# IARC_GR_Shield_SMD.net
KiCad netlist of a schematic drawn in EAGLE
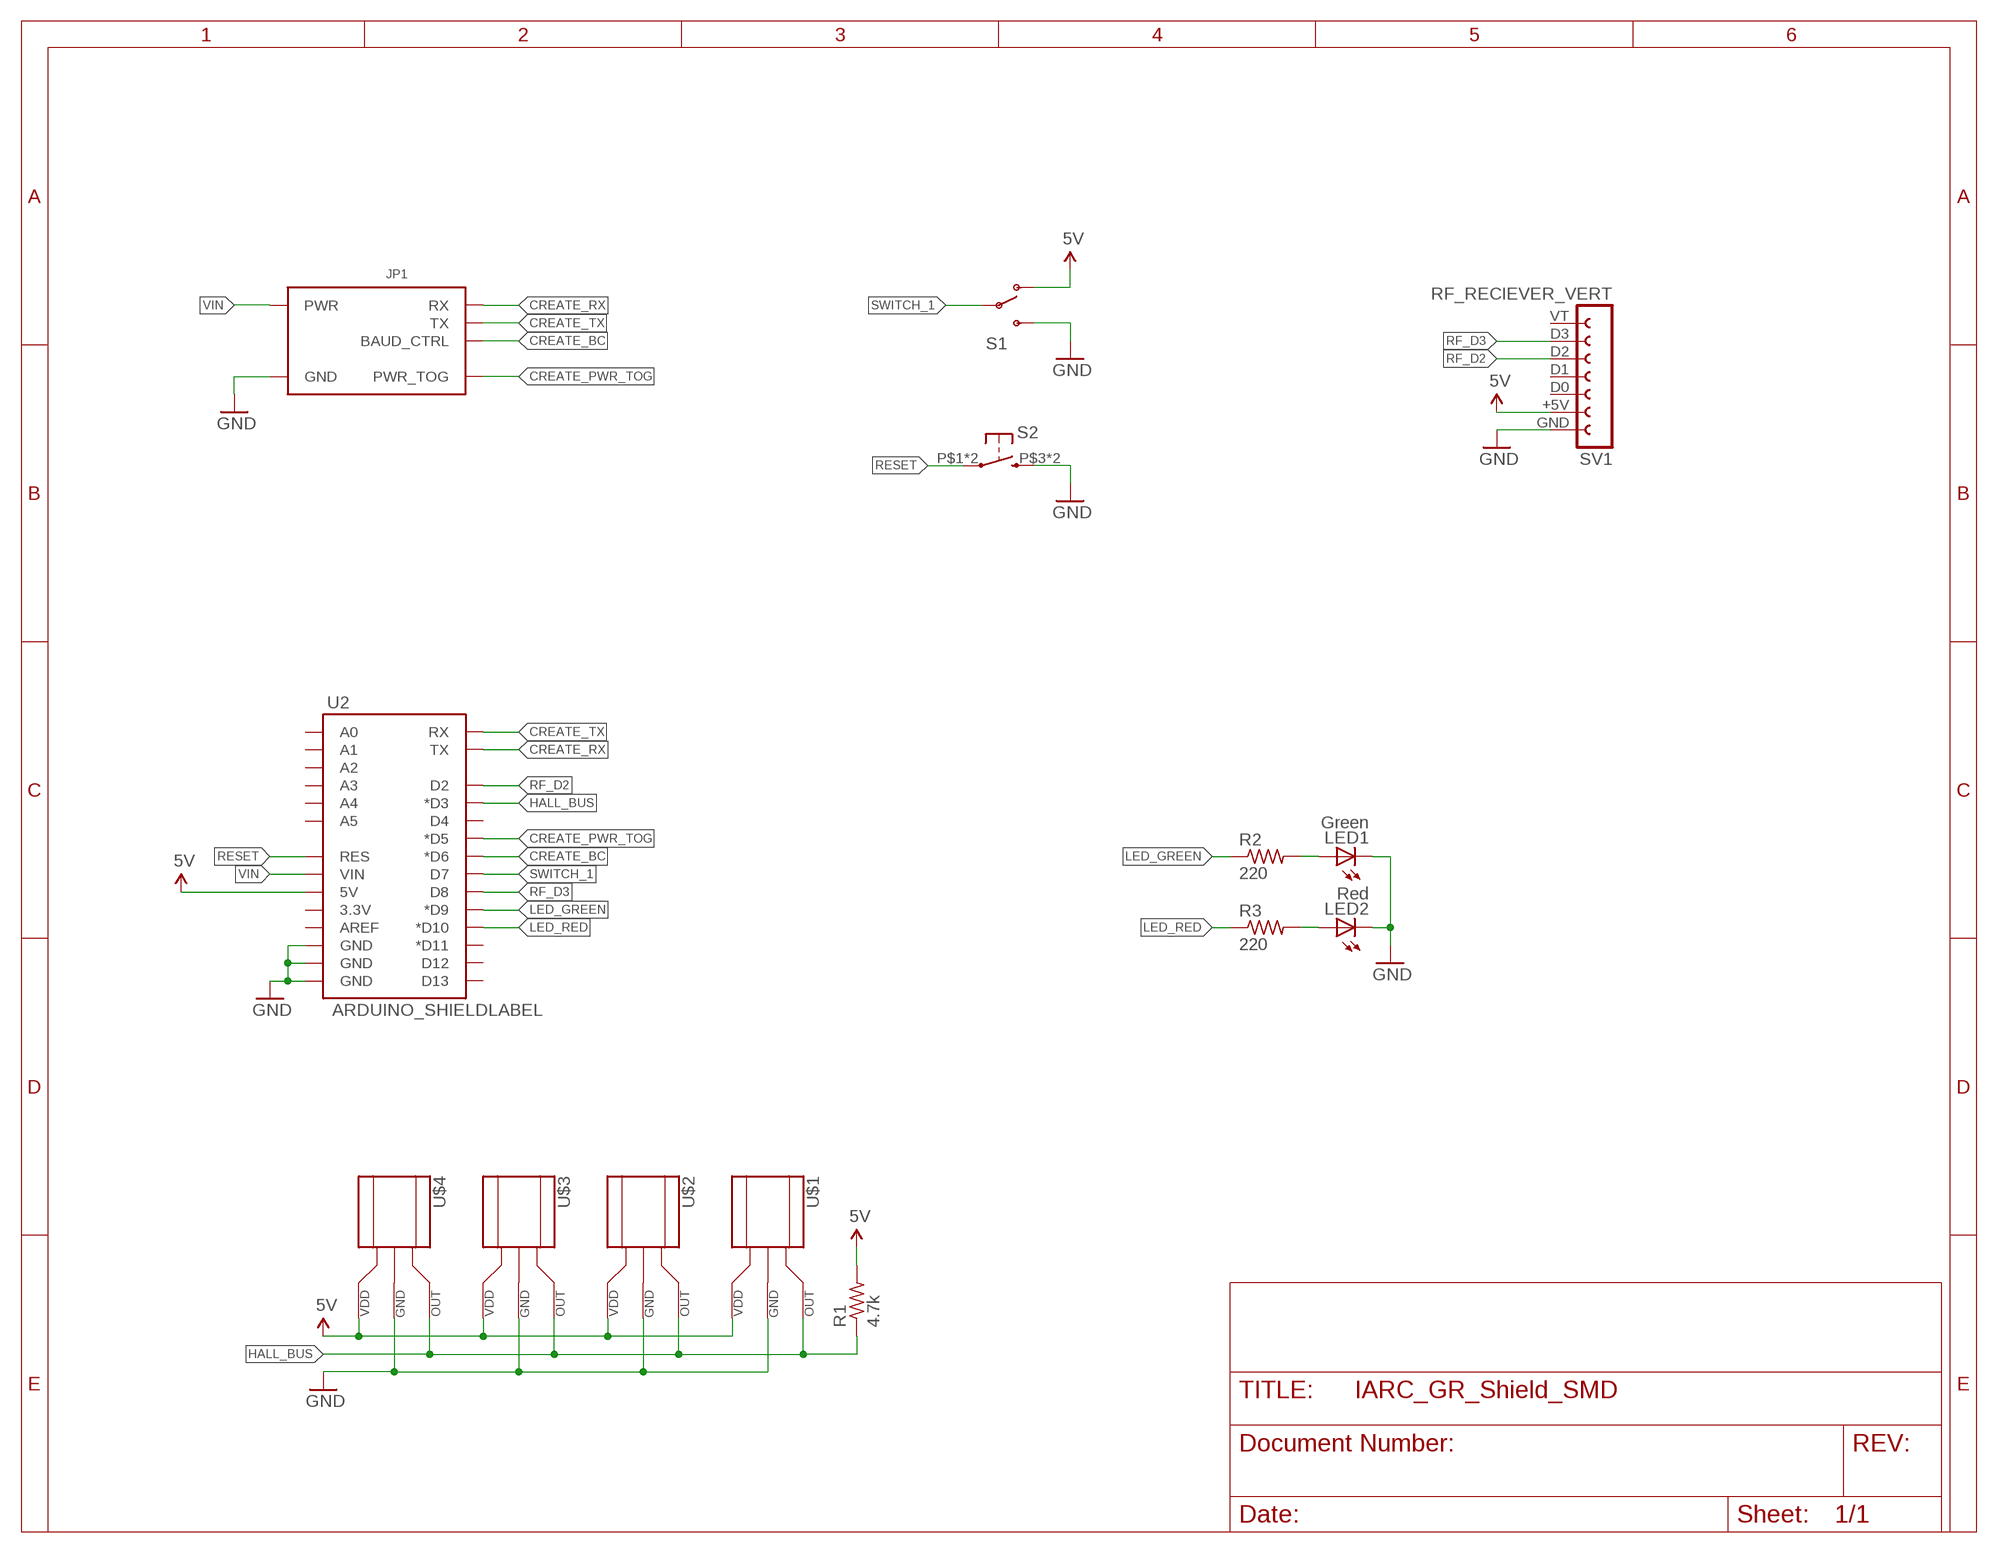
[diagram p0: schematic, sheet 1]

(export (version "E")
  (design (tool "Eeschema 10.0.6"))
  (components
    (comp (ref "JP1")
      (value "IROBOT_CREATE_IARC_HOOKUP")
      (footprint "eagle-import:2X5-SHROUDED")
      (libsource (lib "eagle-import") (part "IROBOT_CREATE_IARC_HOOKUP"))
    )
    (comp (ref "LED1")
      (value "Green")
      (footprint "eagle-import:CHIPLED_0603")
      (libsource (lib "eagle-import") (part "LEDCHIPLED_0603"))
    )
    (comp (ref "LED2")
      (value "Red")
      (footprint "eagle-import:CHIPLED_0603")
      (libsource (lib "eagle-import") (part "LEDCHIPLED_0603"))
    )
    (comp (ref "R1")
      (value "4.7k")
      (footprint "eagle-import:R0603")
      (libsource (lib "eagle-import") (part "R-USR0603"))
    )
    (comp (ref "R2")
      (value "220")
      (footprint "eagle-import:R0603")
      (fields (field (name "DIGIKEY#") "P220HCT-ND"))
      (libsource (lib "eagle-import") (part "R-USR0603"))
    )
    (comp (ref "R3")
      (value "220")
      (footprint "eagle-import:R0603")
      (fields (field (name "DIGIKEY#") "P220HCT-ND"))
      (libsource (lib "eagle-import") (part "R-USR0603"))
    )
    (comp (ref "S1")
      (value "SWITCH-SPDTTHRU-VERT")
      (footprint "eagle-import:SWITCH-SPDT_THRU-VERT")
      (libsource (lib "eagle-import") (part "SWITCH-SPDTTHRU-VERT"))
    )
    (comp (ref "S2")
      (value "TACT_BUTTON_SMD")
      (footprint "eagle-import:SIMPLE_BUTTON_SMD")
      (libsource (lib "eagle-import") (part "TACT_BUTTON_SMD"))
    )
    (comp (ref "SV1")
      (value "RF_RECIEVER_VERT")
      (footprint "eagle-import:RF_RECIEVER_VERT")
      (fields (field (name "MF") "Sulins") (field (name "MPN") "PPTC071LFBN-RC"))
      (libsource (lib "eagle-import") (part "RF_RECIEVER_VERT"))
    )
    (comp (ref "U$1")
      (value "HALL_EFFECTHEADER")
      (footprint "eagle-import:1X03")
      (fields (field (name "MFR") "FCI") (field (name "MPN") "68000-103HLF"))
      (libsource (lib "eagle-import") (part "HALL_EFFECTHEADER"))
    )
    (comp (ref "U$2")
      (value "HALL_EFFECTHEADER")
      (footprint "eagle-import:1X03")
      (fields (field (name "MFR") "FCI") (field (name "MPN") "68000-103HLF"))
      (libsource (lib "eagle-import") (part "HALL_EFFECTHEADER"))
    )
    (comp (ref "U$3")
      (value "HALL_EFFECTHEADER")
      (footprint "eagle-import:1X03")
      (fields (field (name "MFR") "FCI") (field (name "MPN") "68000-103HLF"))
      (libsource (lib "eagle-import") (part "HALL_EFFECTHEADER"))
    )
    (comp (ref "U$4")
      (value "HALL_EFFECTHEADER")
      (footprint "eagle-import:1X03")
      (fields (field (name "MFR") "FCI") (field (name "MPN") "68000-103HLF"))
      (libsource (lib "eagle-import") (part "HALL_EFFECTHEADER"))
    )
    (comp (ref "U2")
      (value "ARDUINO_SHIELDLABEL")
      (footprint "eagle-import:DUEMILANOVE_SHIELD")
      (libsource (lib "eagle-import") (part "ARDUINO_SHIELDLABEL"))
    )
  )
  (nets
    (net (code "1") (name "5V") (class "Default")
      (node (ref "R1") (pin "2") (pinfunction "2_2") (pintype "passive"))
      (node (ref "S1") (pin "1") (pinfunction "O_1") (pintype "passive"))
      (node (ref "SV1") (pin "+5V") (pinfunction "+5V_+5V") (pintype "power_in"))
      (node (ref "U$1") (pin "1") (pinfunction "VDD_1") (pintype "power_in"))
      (node (ref "U$2") (pin "1") (pinfunction "VDD_1") (pintype "power_in"))
      (node (ref "U$3") (pin "1") (pinfunction "VDD_1") (pintype "power_in"))
      (node (ref "U$4") (pin "1") (pinfunction "VDD_1") (pintype "power_in"))
      (node (ref "U2") (pin "5V") (pinfunction "5V_5V") (pintype "bidirectional"))
    )
    (net (code "2") (name "CREATE_BC") (class "Default")
      (node (ref "JP1") (pin "3") (pinfunction "BAUD_CTRL_3") (pintype "bidirectional"))
      (node (ref "U2") (pin "D6") (pinfunction "*D6_D6") (pintype "bidirectional"))
    )
    (net (code "3") (name "CREATE_PWR_TOG") (class "Default")
      (node (ref "JP1") (pin "5") (pinfunction "PWR_TOG_5") (pintype "bidirectional"))
      (node (ref "U2") (pin "D5") (pinfunction "*D5_D5") (pintype "bidirectional"))
    )
    (net (code "4") (name "CREATE_RX") (class "Default")
      (node (ref "JP1") (pin "4") (pinfunction "RX_4") (pintype "bidirectional"))
      (node (ref "U2") (pin "TX") (pinfunction "TX_TX") (pintype "bidirectional"))
    )
    (net (code "5") (name "CREATE_TX") (class "Default")
      (node (ref "JP1") (pin "1") (pinfunction "TX_1") (pintype "bidirectional"))
      (node (ref "U2") (pin "RX") (pinfunction "RX_RX") (pintype "bidirectional"))
    )
    (net (code "6") (name "GND") (class "Default")
      (node (ref "JP1") (pin "2") (pinfunction "GND_2") (pintype "power_in"))
      (node (ref "LED1") (pin "C") (pinfunction "C_C") (pintype "passive"))
      (node (ref "LED2") (pin "C") (pinfunction "C_C") (pintype "passive"))
      (node (ref "S1") (pin "3") (pinfunction "S_3") (pintype "passive"))
      (node (ref "S2") (pin "P$3") (pinfunction "S_P$3") (pintype "passive"))
      (node (ref "S2") (pin "P$4") (pinfunction "S_P$4") (pintype "passive"))
      (node (ref "SV1") (pin "GND") (pinfunction "GND_GND") (pintype "power_in"))
      (node (ref "U$1") (pin "2") (pinfunction "GND_2") (pintype "power_in"))
      (node (ref "U$2") (pin "2") (pinfunction "GND_2") (pintype "power_in"))
      (node (ref "U$3") (pin "2") (pinfunction "GND_2") (pintype "power_in"))
      (node (ref "U$4") (pin "2") (pinfunction "GND_2") (pintype "power_in"))
      (node (ref "U2") (pin "GND@0") (pinfunction "GND_GND@0") (pintype "bidirectional"))
      (node (ref "U2") (pin "GND@1") (pinfunction "GND_GND@1") (pintype "bidirectional"))
      (node (ref "U2") (pin "GND@2") (pinfunction "GND_GND@2") (pintype "bidirectional"))
    )
    (net (code "7") (name "HALL_BUS") (class "Default")
      (node (ref "R1") (pin "1") (pinfunction "1_1") (pintype "passive"))
      (node (ref "U$1") (pin "3") (pinfunction "OUT_3") (pintype "passive"))
      (node (ref "U$2") (pin "3") (pinfunction "OUT_3") (pintype "passive"))
      (node (ref "U$3") (pin "3") (pinfunction "OUT_3") (pintype "passive"))
      (node (ref "U$4") (pin "3") (pinfunction "OUT_3") (pintype "passive"))
      (node (ref "U2") (pin "D3") (pinfunction "*D3_D3") (pintype "bidirectional"))
    )
    (net (code "8") (name "LED_GREEN") (class "Default")
      (node (ref "R2") (pin "1") (pinfunction "1_1") (pintype "passive"))
      (node (ref "U2") (pin "D9") (pinfunction "*D9_D9") (pintype "bidirectional"))
    )
    (net (code "9") (name "LED_RED") (class "Default")
      (node (ref "R3") (pin "1") (pinfunction "1_1") (pintype "passive"))
      (node (ref "U2") (pin "D10") (pinfunction "*D10_D10") (pintype "bidirectional"))
    )
    (net (code "10") (name "Net-(LED1-PadA)") (class "Default")
      (node (ref "LED1") (pin "A") (pinfunction "A_A") (pintype "passive"))
      (node (ref "R2") (pin "2") (pinfunction "2_2") (pintype "passive"))
    )
    (net (code "11") (name "Net-(LED2-PadA)") (class "Default")
      (node (ref "LED2") (pin "A") (pinfunction "A_A") (pintype "passive"))
      (node (ref "R3") (pin "2") (pinfunction "2_2") (pintype "passive"))
    )
    (net (code "12") (name "RESET") (class "Default")
      (node (ref "S2") (pin "P$1") (pinfunction "P_P$1") (pintype "passive"))
      (node (ref "S2") (pin "P$2") (pinfunction "P_P$2") (pintype "passive"))
      (node (ref "U2") (pin "RES") (pinfunction "RES_RES") (pintype "bidirectional"))
    )
    (net (code "13") (name "RF_D2") (class "Default")
      (node (ref "SV1") (pin "D2") (pinfunction "D2_D2") (pintype "bidirectional"))
      (node (ref "U2") (pin "D2") (pinfunction "D2_D2") (pintype "bidirectional"))
    )
    (net (code "14") (name "RF_D3") (class "Default")
      (node (ref "SV1") (pin "D3") (pinfunction "D3_D3") (pintype "bidirectional"))
      (node (ref "U2") (pin "D8") (pinfunction "D8_D8") (pintype "bidirectional"))
    )
    (net (code "15") (name "SWITCH_1") (class "Default")
      (node (ref "S1") (pin "2") (pinfunction "P_2") (pintype "passive"))
      (node (ref "U2") (pin "D7") (pinfunction "D7_D7") (pintype "bidirectional"))
    )
    (net (code "16") (name "VIN") (class "Default")
      (node (ref "JP1") (pin "6") (pinfunction "PWR_6") (pintype "power_in"))
      (node (ref "U2") (pin "VIN") (pinfunction "VIN_VIN") (pintype "bidirectional"))
    )
    (net (code "17") (name "unconnected-(SV1-PadD0)") (class "Default")
      (node (ref "SV1") (pin "D0") (pinfunction "D0_D0") (pintype "bidirectional"))
    )
    (net (code "18") (name "unconnected-(SV1-PadD1)") (class "Default")
      (node (ref "SV1") (pin "D1") (pinfunction "D1_D1") (pintype "bidirectional"))
    )
    (net (code "19") (name "unconnected-(SV1-PadVT)") (class "Default")
      (node (ref "SV1") (pin "VT") (pinfunction "VT_VT") (pintype "passive"))
    )
    (net (code "20") (name "unconnected-(U2-*D11-PadD11)") (class "Default")
      (node (ref "U2") (pin "D11") (pinfunction "*D11_D11") (pintype "bidirectional"))
    )
    (net (code "21") (name "unconnected-(U2-Pad3.3V)") (class "Default")
      (node (ref "U2") (pin "3.3V") (pinfunction "3.3V_3.3V") (pintype "bidirectional"))
    )
    (net (code "22") (name "unconnected-(U2-PadA0)") (class "Default")
      (node (ref "U2") (pin "A0") (pinfunction "A0_A0") (pintype "bidirectional"))
    )
    (net (code "23") (name "unconnected-(U2-PadA1)") (class "Default")
      (node (ref "U2") (pin "A1") (pinfunction "A1_A1") (pintype "bidirectional"))
    )
    (net (code "24") (name "unconnected-(U2-PadA2)") (class "Default")
      (node (ref "U2") (pin "A2") (pinfunction "A2_A2") (pintype "bidirectional"))
    )
    (net (code "25") (name "unconnected-(U2-PadA3)") (class "Default")
      (node (ref "U2") (pin "A3") (pinfunction "A3_A3") (pintype "bidirectional"))
    )
    (net (code "26") (name "unconnected-(U2-PadA4)") (class "Default")
      (node (ref "U2") (pin "A4") (pinfunction "A4_A4") (pintype "bidirectional"))
    )
    (net (code "27") (name "unconnected-(U2-PadA5)") (class "Default")
      (node (ref "U2") (pin "A5") (pinfunction "A5_A5") (pintype "bidirectional"))
    )
    (net (code "28") (name "unconnected-(U2-PadAREF)") (class "Default")
      (node (ref "U2") (pin "AREF") (pinfunction "AREF_AREF") (pintype "bidirectional"))
    )
    (net (code "29") (name "unconnected-(U2-PadD4)") (class "Default")
      (node (ref "U2") (pin "D4") (pinfunction "D4_D4") (pintype "bidirectional"))
    )
    (net (code "30") (name "unconnected-(U2-PadD12)") (class "Default")
      (node (ref "U2") (pin "D12") (pinfunction "D12_D12") (pintype "bidirectional"))
    )
    (net (code "31") (name "unconnected-(U2-PadD13)") (class "Default")
      (node (ref "U2") (pin "D13") (pinfunction "D13_D13") (pintype "bidirectional"))
    )
  )
)
